# DC-Motor-DRV.net
KiCad netlist of a schematic drawn in Altium Designer
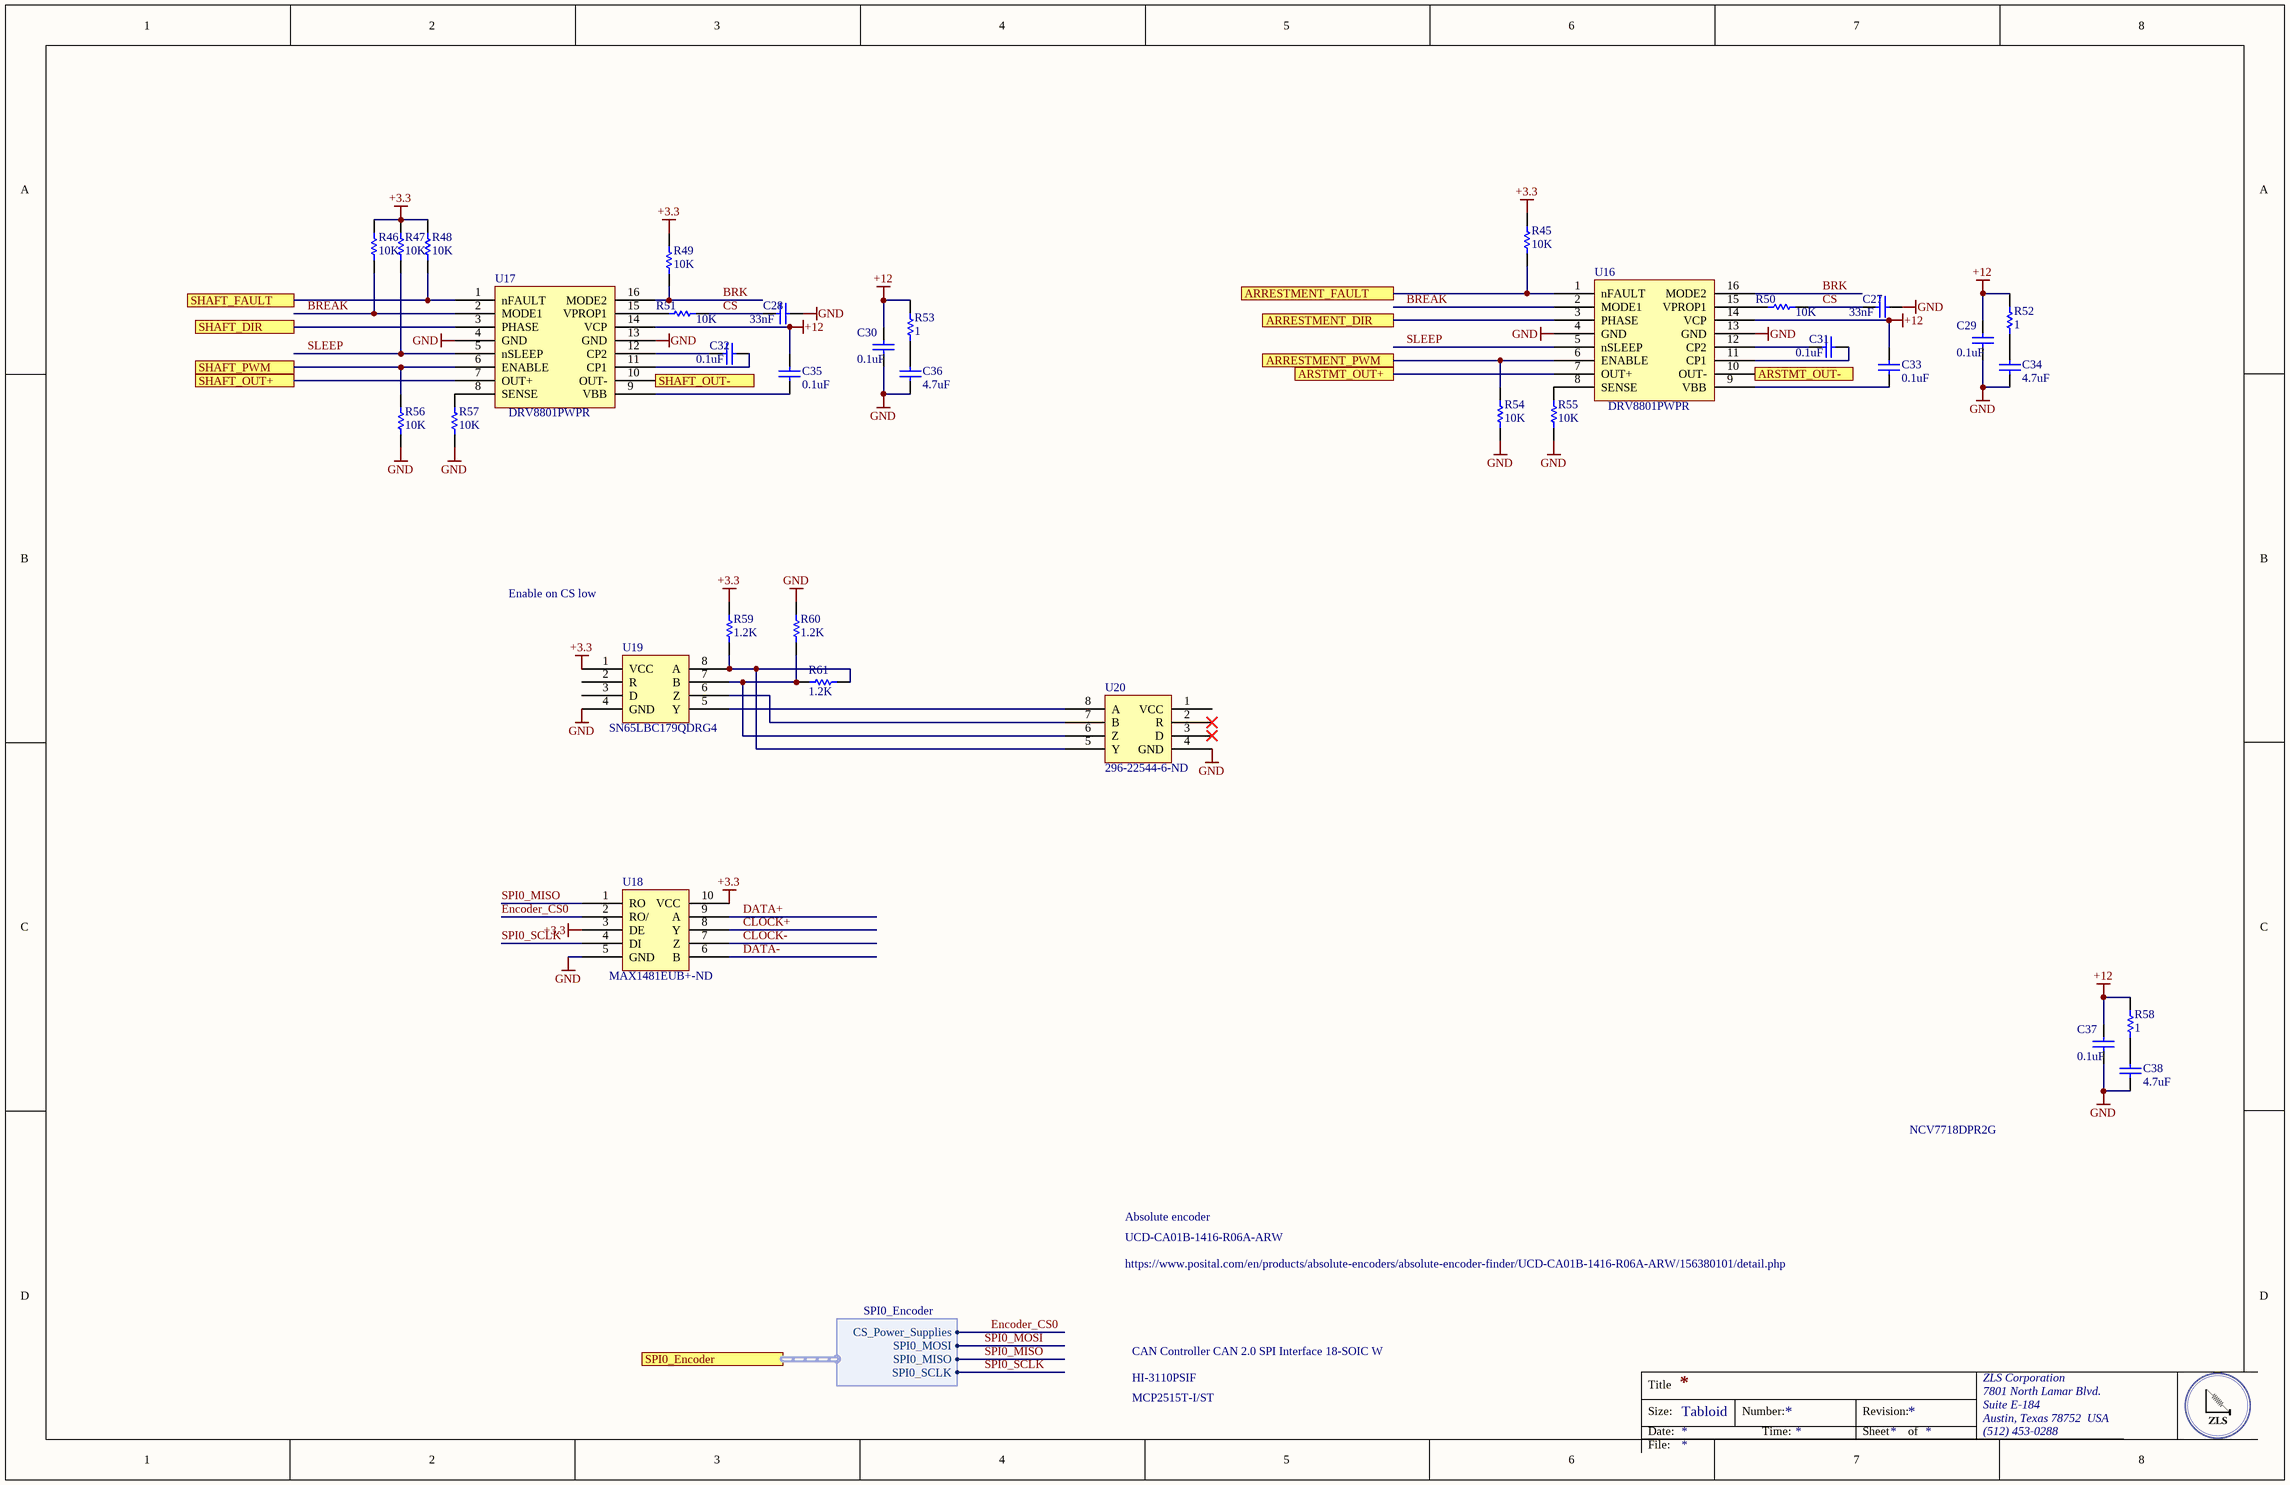
[diagram p0: DC-Motor-DRV.SchDoc]

(export (version "E")
  (design (tool "Eeschema 10.0.6"))
  (components
    (comp (ref "C27")
      (value "33nF")
      (footprint "CAPC0402(1005)60_L")
      (description "CAP CER 0.1UF 10V X7R 0402")
      (fields
        (field (name "MANUFACTURER") "Murata Electronics North America")
        (field (name "MANUFACTURER PART NUMBER") "GRM155R71A104KA01D")
      )
      (libsource (lib "Altium Content Vault") (part "CMP-1034-00252-1"))
    )
    (comp (ref "C28")
      (value "33nF")
      (footprint "CAPC0402(1005)60_L")
      (description "CAP CER 0.1UF 10V X7R 0402")
      (fields
        (field (name "MANUFACTURER") "Murata Electronics North America")
        (field (name "MANUFACTURER PART NUMBER") "GRM155R71A104KA01D")
      )
      (libsource (lib "Altium Content Vault") (part "CMP-1034-00252-1"))
    )
    (comp (ref "C29")
      (value "0.1uF")
      (footprint "CAPC0402(1005)60_L")
      (description "CAP CER 0.1UF 10V X7R 0402")
      (fields
        (field (name "MANUFACTURER") "Murata Electronics North America")
        (field (name "MANUFACTURER PART NUMBER") "GRM155R71A104KA01D")
      )
      (libsource (lib "Altium Content Vault") (part "CMP-1034-00252-1"))
    )
    (comp (ref "C30")
      (value "0.1uF")
      (footprint "CAPC0402(1005)60_L")
      (description "CAP CER 0.1UF 10V X7R 0402")
      (fields
        (field (name "MANUFACTURER") "Murata Electronics North America")
        (field (name "MANUFACTURER PART NUMBER") "GRM155R71A104KA01D")
      )
      (libsource (lib "Altium Content Vault") (part "CMP-1034-00252-1"))
    )
    (comp (ref "C31")
      (value "0.1uF")
      (footprint "CAPC0402(1005)60_L")
      (description "CAP CER 0.1UF 10V X7R 0402")
      (fields
        (field (name "MANUFACTURER") "Murata Electronics North America")
        (field (name "MANUFACTURER PART NUMBER") "GRM155R71A104KA01D")
      )
      (libsource (lib "Altium Content Vault") (part "CMP-1034-00252-1"))
    )
    (comp (ref "C32")
      (value "0.1uF")
      (footprint "CAPC0402(1005)60_L")
      (description "CAP CER 0.1UF 10V X7R 0402")
      (fields
        (field (name "MANUFACTURER") "Murata Electronics North America")
        (field (name "MANUFACTURER PART NUMBER") "GRM155R71A104KA01D")
      )
      (libsource (lib "Altium Content Vault") (part "CMP-1034-00252-1"))
    )
    (comp (ref "C33")
      (value "0.1uF")
      (footprint "CAPC0402(1005)60_L")
      (description "CAP CER 0.1UF 10V X7R 0402")
      (fields
        (field (name "MANUFACTURER") "Murata Electronics North America")
        (field (name "MANUFACTURER PART NUMBER") "GRM155R71A104KA01D")
      )
      (libsource (lib "Altium Content Vault") (part "CMP-1034-00252-1"))
    )
    (comp (ref "C34")
      (value "4.7uF")
      (footprint "CAPC0402(1005)60_L")
      (description "CAP CER 0.1UF 10V X7R 0402")
      (fields
        (field (name "MANUFACTURER") "Murata Electronics North America")
        (field (name "MANUFACTURER PART NUMBER") "GRM155R71A104KA01D")
      )
      (libsource (lib "Altium Content Vault") (part "CMP-1034-00252-1"))
    )
    (comp (ref "C35")
      (value "0.1uF")
      (footprint "CAPC0402(1005)60_L")
      (description "CAP CER 0.1UF 10V X7R 0402")
      (fields
        (field (name "MANUFACTURER") "Murata Electronics North America")
        (field (name "MANUFACTURER PART NUMBER") "GRM155R71A104KA01D")
      )
      (libsource (lib "Altium Content Vault") (part "CMP-1034-00252-1"))
    )
    (comp (ref "C36")
      (value "4.7uF")
      (footprint "CAPC0402(1005)60_L")
      (description "CAP CER 0.1UF 10V X7R 0402")
      (fields
        (field (name "MANUFACTURER") "Murata Electronics North America")
        (field (name "MANUFACTURER PART NUMBER") "GRM155R71A104KA01D")
      )
      (libsource (lib "Altium Content Vault") (part "CMP-1034-00252-1"))
    )
    (comp (ref "C37")
      (value "0.1uF")
      (footprint "CAPC0402(1005)60_L")
      (description "CAP CER 0.1UF 10V X7R 0402")
      (fields
        (field (name "MANUFACTURER") "Murata Electronics North America")
        (field (name "MANUFACTURER PART NUMBER") "GRM155R71A104KA01D")
      )
      (libsource (lib "Altium Content Vault") (part "CMP-1034-00252-1"))
    )
    (comp (ref "C38")
      (value "4.7uF")
      (footprint "CAPC0402(1005)60_L")
      (description "CAP CER 0.1UF 10V X7R 0402")
      (fields
        (field (name "MANUFACTURER") "Murata Electronics North America")
        (field (name "MANUFACTURER PART NUMBER") "GRM155R71A104KA01D")
      )
      (libsource (lib "Altium Content Vault") (part "CMP-1034-00252-1"))
    )
    (comp (ref "R45")
      (value "10K")
      (footprint "RESC0402(1005)_M")
      (libsource (lib "Altium Content Vault") (part "CMP-1011-00651-1"))
    )
    (comp (ref "R46")
      (value "10K")
      (footprint "RESC0402(1005)_M")
      (libsource (lib "Altium Content Vault") (part "CMP-1011-00651-1"))
    )
    (comp (ref "R47")
      (value "10K")
      (footprint "RESC0402(1005)_M")
      (libsource (lib "Altium Content Vault") (part "CMP-1011-00651-1"))
    )
    (comp (ref "R48")
      (value "10K")
      (footprint "RESC0402(1005)_M")
      (libsource (lib "Altium Content Vault") (part "CMP-1011-00651-1"))
    )
    (comp (ref "R49")
      (value "10K")
      (footprint "RESC0402(1005)_M")
      (libsource (lib "Altium Content Vault") (part "CMP-1011-00651-1"))
    )
    (comp (ref "R50")
      (value "10K")
      (footprint "RESC0402(1005)_M")
      (libsource (lib "Altium Content Vault") (part "CMP-1011-00651-1"))
    )
    (comp (ref "R51")
      (value "10K")
      (footprint "RESC0402(1005)_M")
      (libsource (lib "Altium Content Vault") (part "CMP-1011-00651-1"))
    )
    (comp (ref "R52")
      (value "1")
      (footprint "RESC0402(1005)_M")
      (libsource (lib "Altium Content Vault") (part "CMP-1011-00651-1"))
    )
    (comp (ref "R53")
      (value "1")
      (footprint "RESC0402(1005)_M")
      (libsource (lib "Altium Content Vault") (part "CMP-1011-00651-1"))
    )
    (comp (ref "R54")
      (value "10K")
      (footprint "RESC0402(1005)_M")
      (libsource (lib "Altium Content Vault") (part "CMP-1011-00651-1"))
    )
    (comp (ref "R55")
      (value "10K")
      (footprint "RESC0402(1005)_M")
      (libsource (lib "Altium Content Vault") (part "CMP-1011-00651-1"))
    )
    (comp (ref "R56")
      (value "10K")
      (footprint "RESC0402(1005)_M")
      (libsource (lib "Altium Content Vault") (part "CMP-1011-00651-1"))
    )
    (comp (ref "R57")
      (value "10K")
      (footprint "RESC0402(1005)_M")
      (libsource (lib "Altium Content Vault") (part "CMP-1011-00651-1"))
    )
    (comp (ref "R58")
      (value "1")
      (footprint "RESC0402(1005)_M")
      (libsource (lib "Altium Content Vault") (part "CMP-1011-00651-1"))
    )
    (comp (ref "R59")
      (value "1.2K")
      (footprint "RESC0402(1005)_M")
      (libsource (lib "Altium Content Vault") (part "CMP-1011-00651-1"))
    )
    (comp (ref "R60")
      (value "1.2K")
      (footprint "RESC0402(1005)_M")
      (libsource (lib "Altium Content Vault") (part "CMP-1011-00651-1"))
    )
    (comp (ref "R61")
      (value "1.2K")
      (footprint "RESC0402(1005)_M")
      (libsource (lib "Altium Content Vault") (part "CMP-1011-00651-1"))
    )
    (comp (ref "U16")
      (value "DRV8801PWPR")
      (footprint "DRV8801PWPR")
      (fields (field (name "MANUFACTURER") "Texas Instruments") (field (name "BASE PART NUMBER") "DRV8801"))
      (libsource (lib "ZLS_Schematic_lib") (part "DRV8801PWPR"))
    )
    (comp (ref "U17")
      (value "DRV8801PWPR")
      (footprint "DRV8801PWPR")
      (fields (field (name "MANUFACTURER") "Texas Instruments") (field (name "BASE PART NUMBER") "DRV8801"))
      (libsource (lib "ZLS_Schematic_lib") (part "DRV8801PWPR"))
    )
    (comp (ref "U18")
      (value "MAX1481EUB+")
      (footprint "MAX1486EUB+")
      (fields
        (field (name "SUPPLIER PART NUMBER 1") "MAX1481EUB+-ND")
        (field (name "MANUFACTURER") "Maxim Integrated")
        (field (name "BASE PART NUMBER") "MAX1481")
      )
      (libsource (lib "ZLS_Schematic_lib") (part "MAX1481EUB+"))
    )
    (comp (ref "U19")
      (value "SN65LBC179QDRG4")
      (footprint "SN65LBC179QDRG4")
      (fields
        (field (name "MANUFACTURER") "Texas Instruments")
        (field (name "BASE PART NUMBER") "SN65LBC179")
      )
      (libsource (lib "") (part "SN65LBC179QDRG4_1"))
    )
    (comp (ref "U20")
      (value "SN65LBC179QDRG4")
      (footprint "SN65LBC179QDRG4")
      (fields
        (field (name "SUPPLIER PART NUMBER 1") "296-22544-6-ND")
        (field (name "MANUFACTURER") "Texas Instruments")
        (field (name "BASE PART NUMBER") "SN65LBC179")
      )
      (libsource (lib "ZLS_Schematic_lib") (part "SN65LBC179QDRG4"))
    )
  )
  (nets
    (net (code "2") (name "+3.3") (class "Default")
      (node (ref "R45") (pin "2") (pinfunction "2_2") (pintype "passive"))
      (node (ref "R46") (pin "2") (pinfunction "2_2") (pintype "passive"))
      (node (ref "R47") (pin "2") (pinfunction "2_2") (pintype "passive"))
      (node (ref "R48") (pin "2") (pinfunction "2_2") (pintype "passive"))
      (node (ref "R49") (pin "2") (pinfunction "2_2") (pintype "passive"))
      (node (ref "R59") (pin "2") (pinfunction "2_2") (pintype "passive"))
      (node (ref "U18") (pin "10") (pinfunction "VCC_10") (pintype "passive"))
      (node (ref "U18") (pin "3") (pinfunction "DE_3") (pintype "passive"))
      (node (ref "U19") (pin "1") (pinfunction "VCC_1") (pintype "passive"))
    )
    (net (code "3") (name "+12") (class "Default")
      (node (ref "C29") (pin "2") (pinfunction "2_2") (pintype "passive"))
      (node (ref "C30") (pin "2") (pinfunction "2_2") (pintype "passive"))
      (node (ref "C33") (pin "2") (pinfunction "2_2") (pintype "passive"))
      (node (ref "C35") (pin "2") (pinfunction "2_2") (pintype "passive"))
      (node (ref "C37") (pin "2") (pinfunction "2_2") (pintype "passive"))
      (node (ref "R52") (pin "2") (pinfunction "2_2") (pintype "passive"))
      (node (ref "R53") (pin "2") (pinfunction "2_2") (pintype "passive"))
      (node (ref "R58") (pin "2") (pinfunction "2_2") (pintype "passive"))
      (node (ref "U16") (pin "14") (pinfunction "VCP_14") (pintype "passive"))
      (node (ref "U17") (pin "14") (pinfunction "VCP_14") (pintype "passive"))
    )
    (net (code "4") (name "/ARRESTMENT_DIR") (class "Default")
      (node (ref "U16") (pin "3") (pinfunction "PHASE_3") (pintype "passive"))
    )
    (net (code "5") (name "/ARRESTMENT_FAULT") (class "Default")
      (node (ref "R45") (pin "1") (pinfunction "1_1") (pintype "passive"))
      (node (ref "U16") (pin "1") (pinfunction "nFAULT_1") (pintype "passive"))
    )
    (net (code "6") (name "/ARRESTMENT_PWM") (class "Default")
      (node (ref "R54") (pin "2") (pinfunction "2_2") (pintype "passive"))
      (node (ref "U16") (pin "6") (pinfunction "ENABLE_6") (pintype "passive"))
    )
    (net (code "7") (name "/ARSTMT_OUT+") (class "Default")
      (node (ref "U16") (pin "7") (pinfunction "OUT+_7") (pintype "passive"))
    )
    (net (code "8") (name "/ARSTMT_OUT-") (class "Default")
      (node (ref "U16") (pin "10") (pinfunction "OUT-_10") (pintype "passive"))
    )
    (net (code "9") (name "/BREAK") (class "Default")
      (node (ref "R46") (pin "1") (pinfunction "1_1") (pintype "passive"))
      (node (ref "U16") (pin "2") (pinfunction "MODE1_2") (pintype "passive"))
      (node (ref "U17") (pin "2") (pinfunction "MODE1_2") (pintype "passive"))
    )
    (net (code "10") (name "/BRK") (class "Default")
      (node (ref "R49") (pin "1") (pinfunction "1_1") (pintype "passive"))
      (node (ref "U16") (pin "16") (pinfunction "MODE2_16") (pintype "passive"))
      (node (ref "U17") (pin "16") (pinfunction "MODE2_16") (pintype "passive"))
    )
    (net (code "11") (name "/CLOCK+") (class "Default")
      (node (ref "U18") (pin "8") (pinfunction "Y_8") (pintype "passive"))
    )
    (net (code "12") (name "/CLOCK-") (class "Default")
      (node (ref "U18") (pin "7") (pinfunction "Z_7") (pintype "passive"))
    )
    (net (code "13") (name "/CS") (class "Default")
      (node (ref "C27") (pin "1") (pinfunction "1_1") (pintype "passive"))
      (node (ref "C28") (pin "1") (pinfunction "1_1") (pintype "passive"))
      (node (ref "R50") (pin "2") (pinfunction "2_2") (pintype "passive"))
      (node (ref "R51") (pin "2") (pinfunction "2_2") (pintype "passive"))
    )
    (net (code "14") (name "/DATA+") (class "Default")
      (node (ref "U18") (pin "9") (pinfunction "A_9") (pintype "passive"))
    )
    (net (code "15") (name "/DATA-") (class "Default")
      (node (ref "U18") (pin "6") (pinfunction "B_6") (pintype "passive"))
    )
    (net (code "16") (name "/Encoder_CS0") (class "Default")
      (node (ref "U18") (pin "2") (pinfunction "RO/_2") (pintype "passive"))
    )
    (net (code "17") (name "/SHAFT_DIR") (class "Default")
      (node (ref "U17") (pin "3") (pinfunction "PHASE_3") (pintype "passive"))
    )
    (net (code "18") (name "/SHAFT_FAULT") (class "Default")
      (node (ref "R48") (pin "1") (pinfunction "1_1") (pintype "passive"))
      (node (ref "U17") (pin "1") (pinfunction "nFAULT_1") (pintype "passive"))
    )
    (net (code "19") (name "/SHAFT_OUT+") (class "Default")
      (node (ref "U17") (pin "7") (pinfunction "OUT+_7") (pintype "passive"))
    )
    (net (code "20") (name "/SHAFT_OUT-") (class "Default")
      (node (ref "U17") (pin "10") (pinfunction "OUT-_10") (pintype "passive"))
    )
    (net (code "21") (name "/SHAFT_PWM") (class "Default")
      (node (ref "R56") (pin "2") (pinfunction "2_2") (pintype "passive"))
      (node (ref "U17") (pin "6") (pinfunction "ENABLE_6") (pintype "passive"))
    )
    (net (code "22") (name "/SLEEP") (class "Default")
      (node (ref "R47") (pin "1") (pinfunction "1_1") (pintype "passive"))
      (node (ref "U16") (pin "5") (pinfunction "nSLEEP_5") (pintype "passive"))
      (node (ref "U17") (pin "5") (pinfunction "nSLEEP_5") (pintype "passive"))
    )
    (net (code "23") (name "/SPI0_MISO") (class "Default")
      (node (ref "U18") (pin "1") (pinfunction "RO_1") (pintype "passive"))
    )
    (net (code "25") (name "/SPI0_SCLK") (class "Default")
      (node (ref "U18") (pin "4") (pinfunction "DI_4") (pintype "passive"))
    )
    (net (code "27") (name "GND") (class "Default")
      (node (ref "C27") (pin "2") (pinfunction "2_2") (pintype "passive"))
      (node (ref "C28") (pin "2") (pinfunction "2_2") (pintype "passive"))
      (node (ref "C29") (pin "1") (pinfunction "1_1") (pintype "passive"))
      (node (ref "C30") (pin "1") (pinfunction "1_1") (pintype "passive"))
      (node (ref "C34") (pin "1") (pinfunction "1_1") (pintype "passive"))
      (node (ref "C36") (pin "1") (pinfunction "1_1") (pintype "passive"))
      (node (ref "C37") (pin "1") (pinfunction "1_1") (pintype "passive"))
      (node (ref "C38") (pin "1") (pinfunction "1_1") (pintype "passive"))
      (node (ref "R54") (pin "1") (pinfunction "1_1") (pintype "passive"))
      (node (ref "R55") (pin "1") (pinfunction "1_1") (pintype "passive"))
      (node (ref "R56") (pin "1") (pinfunction "1_1") (pintype "passive"))
      (node (ref "R57") (pin "1") (pinfunction "1_1") (pintype "passive"))
      (node (ref "R60") (pin "2") (pinfunction "2_2") (pintype "passive"))
      (node (ref "U16") (pin "13") (pinfunction "GND_13") (pintype "passive"))
      (node (ref "U16") (pin "4") (pinfunction "GND_4") (pintype "passive"))
      (node (ref "U17") (pin "13") (pinfunction "GND_13") (pintype "passive"))
      (node (ref "U17") (pin "4") (pinfunction "GND_4") (pintype "passive"))
      (node (ref "U18") (pin "5") (pinfunction "GND_5") (pintype "passive"))
      (node (ref "U19") (pin "4") (pinfunction "GND_4") (pintype "passive"))
      (node (ref "U20") (pin "4") (pinfunction "GND_4") (pintype "passive"))
    )
    (net (code "28") (name "Net-(C34-Pad2)") (class "Default")
      (node (ref "C34") (pin "2") (pinfunction "2_2") (pintype "passive"))
      (node (ref "R52") (pin "1") (pinfunction "1_1") (pintype "passive"))
    )
    (net (code "29") (name "Net-(C36-Pad2)") (class "Default")
      (node (ref "C36") (pin "2") (pinfunction "2_2") (pintype "passive"))
      (node (ref "R53") (pin "1") (pinfunction "1_1") (pintype "passive"))
    )
    (net (code "30") (name "Net-(C38-Pad2)") (class "Default")
      (node (ref "C38") (pin "2") (pinfunction "2_2") (pintype "passive"))
      (node (ref "R58") (pin "1") (pinfunction "1_1") (pintype "passive"))
    )
    (net (code "31") (name "Net-(U16-CP1)") (class "Default")
      (node (ref "C31") (pin "1") (pinfunction "1_1") (pintype "passive"))
      (node (ref "U16") (pin "11") (pinfunction "CP1_11") (pintype "passive"))
    )
    (net (code "32") (name "Net-(U16-CP2)") (class "Default")
      (node (ref "C31") (pin "2") (pinfunction "2_2") (pintype "passive"))
      (node (ref "U16") (pin "12") (pinfunction "CP2_12") (pintype "passive"))
    )
    (net (code "33") (name "Net-(U16-SENSE)") (class "Default")
      (node (ref "R55") (pin "2") (pinfunction "2_2") (pintype "passive"))
      (node (ref "U16") (pin "8") (pinfunction "SENSE_8") (pintype "passive"))
    )
    (net (code "34") (name "Net-(U16-VBB)") (class "Default")
      (node (ref "C33") (pin "1") (pinfunction "1_1") (pintype "passive"))
      (node (ref "U16") (pin "9") (pinfunction "VBB_9") (pintype "passive"))
    )
    (net (code "35") (name "Net-(U16-VPROP1)") (class "Default")
      (node (ref "R50") (pin "1") (pinfunction "1_1") (pintype "passive"))
      (node (ref "U16") (pin "15") (pinfunction "VPROP1_15") (pintype "passive"))
    )
    (net (code "36") (name "Net-(U17-CP1)") (class "Default")
      (node (ref "C32") (pin "1") (pinfunction "1_1") (pintype "passive"))
      (node (ref "U17") (pin "11") (pinfunction "CP1_11") (pintype "passive"))
    )
    (net (code "37") (name "Net-(U17-CP2)") (class "Default")
      (node (ref "C32") (pin "2") (pinfunction "2_2") (pintype "passive"))
      (node (ref "U17") (pin "12") (pinfunction "CP2_12") (pintype "passive"))
    )
    (net (code "38") (name "Net-(U17-SENSE)") (class "Default")
      (node (ref "R57") (pin "2") (pinfunction "2_2") (pintype "passive"))
      (node (ref "U17") (pin "8") (pinfunction "SENSE_8") (pintype "passive"))
    )
    (net (code "39") (name "Net-(U17-VBB)") (class "Default")
      (node (ref "C35") (pin "1") (pinfunction "1_1") (pintype "passive"))
      (node (ref "U17") (pin "9") (pinfunction "VBB_9") (pintype "passive"))
    )
    (net (code "40") (name "Net-(U17-VPROP1)") (class "Default")
      (node (ref "R51") (pin "1") (pinfunction "1_1") (pintype "passive"))
      (node (ref "U17") (pin "15") (pinfunction "VPROP1_15") (pintype "passive"))
    )
    (net (code "41") (name "Net-(U19-A)") (class "Default")
      (node (ref "R59") (pin "1") (pinfunction "1_1") (pintype "passive"))
      (node (ref "R61") (pin "1") (pinfunction "1_1") (pintype "passive"))
      (node (ref "U19") (pin "8") (pinfunction "A_8") (pintype "passive"))
      (node (ref "U20") (pin "5") (pinfunction "Y_5") (pintype "passive"))
    )
    (net (code "42") (name "Net-(U19-B)") (class "Default")
      (node (ref "R60") (pin "1") (pinfunction "1_1") (pintype "passive"))
      (node (ref "R61") (pin "2") (pinfunction "2_2") (pintype "passive"))
      (node (ref "U19") (pin "7") (pinfunction "B_7") (pintype "passive"))
      (node (ref "U20") (pin "6") (pinfunction "Z_6") (pintype "passive"))
    )
    (net (code "43") (name "Net-(U19-Y)") (class "Default")
      (node (ref "U19") (pin "5") (pinfunction "Y_5") (pintype "passive"))
      (node (ref "U20") (pin "8") (pinfunction "A_8") (pintype "passive"))
    )
    (net (code "44") (name "Net-(U19-Z)") (class "Default")
      (node (ref "U19") (pin "6") (pinfunction "Z_6") (pintype "passive"))
      (node (ref "U20") (pin "7") (pinfunction "B_7") (pintype "passive"))
    )
    (net (code "45") (name "unconnected-(U19-D-Pad3)") (class "Default")
      (node (ref "U19") (pin "3") (pinfunction "D_3") (pintype "passive"))
    )
    (net (code "46") (name "unconnected-(U19-R-Pad2)") (class "Default")
      (node (ref "U19") (pin "2") (pinfunction "R_2") (pintype "passive"))
    )
    (net (code "47") (name "unconnected-(U20-D-Pad3)") (class "Default")
      (node (ref "U20") (pin "3") (pinfunction "D_3") (pintype "passive+no_connect"))
    )
    (net (code "48") (name "unconnected-(U20-R-Pad2)") (class "Default")
      (node (ref "U20") (pin "2") (pinfunction "R_2") (pintype "passive+no_connect"))
    )
    (net (code "49") (name "unconnected-(U20-VCC-Pad1)") (class "Default")
      (node (ref "U20") (pin "1") (pinfunction "VCC_1") (pintype "passive"))
    )
  )
)
